# FTDI.net
KiCad netlist of a schematic drawn in Altium Designer
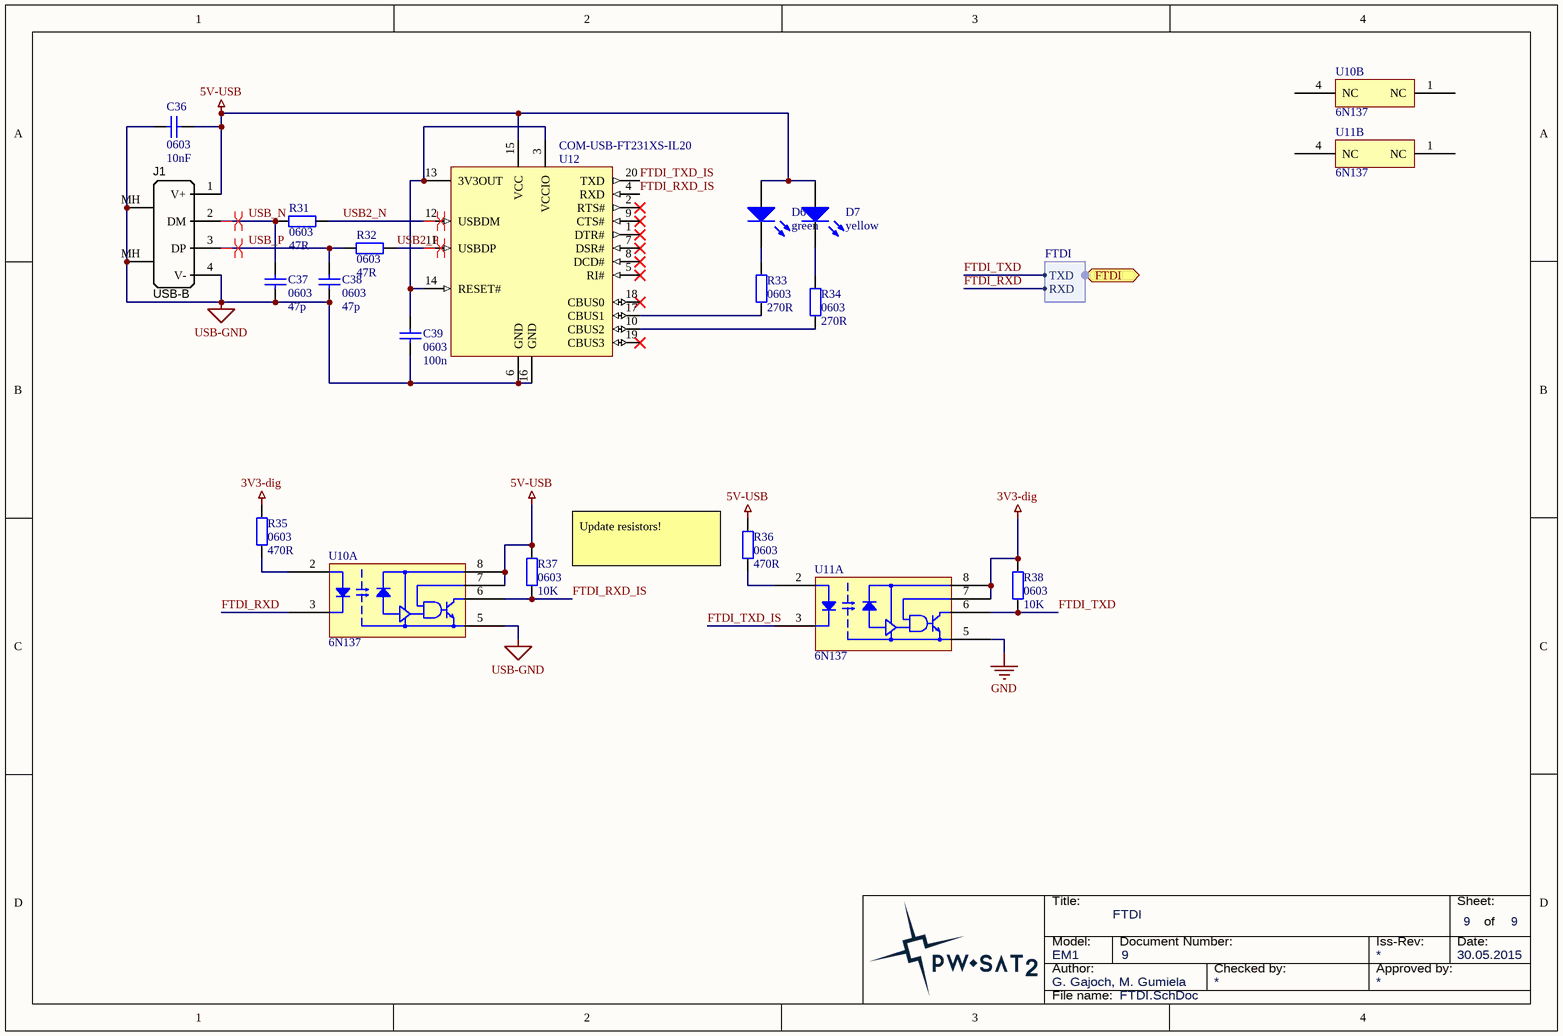
[diagram p0: FTDI.SchDoc]

(export (version "E")
  (design (tool "Eeschema 10.0.6"))
  (components
    (comp (ref "C36")
      (value "0603")
      (footprint "SMD_Capacitor_0603")
      (description "Capacitor")
      (fields (field (name "ALTIUM_VALUE") "10nF") (field (name "PUBLISHER") "Altium Limited"))
      (libsource (lib "Miscellaneous Devices") (part "Cap"))
    )
    (comp (ref "C37")
      (value "0603")
      (footprint "SMD_Capacitor_0603")
      (description "Capacitor")
      (fields (field (name "ALTIUM_VALUE") "47p") (field (name "PUBLISHER") "Altium Limited"))
      (libsource (lib "Miscellaneous Devices") (part "Cap"))
    )
    (comp (ref "C38")
      (value "0603")
      (footprint "SMD_Capacitor_0603")
      (description "Capacitor")
      (fields (field (name "ALTIUM_VALUE") "47p") (field (name "PUBLISHER") "Altium Limited"))
      (libsource (lib "Miscellaneous Devices") (part "Cap"))
    )
    (comp (ref "C39")
      (value "0603")
      (footprint "SMD_Capacitor_0603")
      (description "Capacitor")
      (fields (field (name "ALTIUM_VALUE") "100n") (field (name "PUBLISHER") "Altium Limited"))
      (libsource (lib "Miscellaneous Devices") (part "Cap"))
    )
    (comp (ref "D6")
      (value "green")
      (footprint "LED 0805 GREEN")
      (description "Typical RED, GREEN, YELLOW, AMBER GaAs LED")
      (fields (field (name "PUBLISHER") "Altium Limited"))
      (libsource (lib "Miscellaneous Devices") (part "LED2"))
    )
    (comp (ref "D7")
      (value "yellow")
      (footprint "LED 0805 Yellow")
      (description "Typical RED, GREEN, YELLOW, AMBER GaAs LED")
      (fields (field (name "PUBLISHER") "Altium Limited"))
      (libsource (lib "Miscellaneous Devices") (part "LED2"))
    )
    (comp (ref "J1")
      (value "USB-B")
      (footprint "USB_TypeB_Tyco")
      (description "Connector THT Type B USB connector")
      (libsource (lib "PBL - Connectors") (part "USB_TypeB"))
    )
    (comp (ref "R31")
      (value "0603")
      (footprint "SMD_Resistor_0603")
      (description "Resistor")
      (fields (field (name "ALTIUM_VALUE") "47R") (field (name "PUBLISHER") "Altium Limited"))
      (libsource (lib "Miscellaneous Devices") (part "Res2"))
    )
    (comp (ref "R32")
      (value "0603")
      (footprint "SMD_Resistor_0603")
      (description "Resistor")
      (fields (field (name "ALTIUM_VALUE") "47R") (field (name "PUBLISHER") "Altium Limited"))
      (libsource (lib "Miscellaneous Devices") (part "Res2"))
    )
    (comp (ref "R33")
      (value "0603")
      (footprint "SMD_Resistor_0603")
      (description "Resistor")
      (fields (field (name "ALTIUM_VALUE") "270R") (field (name "PUBLISHER") "Altium Limited"))
      (libsource (lib "") (part "Res2_1"))
    )
    (comp (ref "R34")
      (value "0603")
      (footprint "SMD_Resistor_0603")
      (description "Resistor")
      (fields (field (name "ALTIUM_VALUE") "270R") (field (name "PUBLISHER") "Altium Limited"))
      (libsource (lib "") (part "Res2_1"))
    )
    (comp (ref "R35")
      (value "0603")
      (footprint "SMD_Resistor_0603")
      (description "Resistor")
      (fields (field (name "ALTIUM_VALUE") "470R") (field (name "PUBLISHER") "Altium Limited"))
      (libsource (lib "") (part "Res2_1"))
    )
    (comp (ref "R36")
      (value "0603")
      (footprint "SMD_Resistor_0603")
      (description "Resistor")
      (fields (field (name "ALTIUM_VALUE") "470R") (field (name "PUBLISHER") "Altium Limited"))
      (libsource (lib "") (part "Res2_1"))
    )
    (comp (ref "R37")
      (value "0603")
      (footprint "SMD_Resistor_0603")
      (description "Resistor")
      (fields (field (name "ALTIUM_VALUE") "10K") (field (name "PUBLISHER") "Altium Limited"))
      (libsource (lib "") (part "Res2_1"))
    )
    (comp (ref "R38")
      (value "0603")
      (footprint "SMD_Resistor_0603")
      (description "Resistor")
      (fields (field (name "ALTIUM_VALUE") "10K") (field (name "PUBLISHER") "Altium Limited"))
      (libsource (lib "") (part "Res2_1"))
    )
    (comp (ref "U10")
      (value "6N137")
      (footprint "Surface Mount DIP 8-pin")
      (libsource (lib "6N137") (part "6N137"))
    )
    (comp (ref "U11")
      (value "6N137")
      (footprint "Surface Mount DIP 8-pin")
      (libsource (lib "6N137") (part "6N137"))
    )
    (comp (ref "U12")
      (value "COM-USB-FT231XS-IL20")
      (footprint "SSOP-20_L")
      (libsource (lib "COM-USB-FT231XS-IL20") (part "COM-USB-FT231XS-IL20"))
    )
  )
  (nets
    (net (code "2") (name "/FTDI_RXD") (class "Default")
      (node (ref "U10") (pin "3") (pinfunction "-_3") (pintype "passive"))
    )
    (net (code "3") (name "/FTDI_RXD_IS") (class "Default")
      (node (ref "R37") (pin "1") (pinfunction "1_1") (pintype "passive"))
      (node (ref "U10") (pin "6") (pinfunction "Vo_6") (pintype "passive"))
      (node (ref "U12") (pin "4") (pinfunction "RXD_4") (pintype "input"))
    )
    (net (code "4") (name "/FTDI_TXD") (class "Default")
      (node (ref "R38") (pin "1") (pinfunction "1_1") (pintype "passive"))
      (node (ref "U11") (pin "6") (pinfunction "Vo_6") (pintype "passive"))
    )
    (net (code "5") (name "/FTDI_TXD_IS") (class "Default")
      (node (ref "U11") (pin "3") (pinfunction "-_3") (pintype "passive"))
      (node (ref "U12") (pin "20") (pinfunction "TXD_20") (pintype "output"))
    )
    (net (code "6") (name "/USB2_N") (class "Default")
      (node (ref "R31") (pin "2") (pinfunction "2_2") (pintype "passive"))
      (node (ref "U12") (pin "12") (pinfunction "USBDM_12") (pintype "input"))
    )
    (net (code "7") (name "/USB2_P") (class "Default")
      (node (ref "R32") (pin "2") (pinfunction "2_2") (pintype "passive"))
      (node (ref "U12") (pin "11") (pinfunction "USBDP_11") (pintype "input"))
    )
    (net (code "8") (name "/USB_N") (class "Default")
      (node (ref "C37") (pin "2") (pinfunction "2_2") (pintype "passive"))
      (node (ref "J1") (pin "2") (pinfunction "DM_2") (pintype "passive"))
      (node (ref "R31") (pin "1") (pinfunction "1_1") (pintype "passive"))
    )
    (net (code "9") (name "/USB_P") (class "Default")
      (node (ref "C38") (pin "2") (pinfunction "2_2") (pintype "passive"))
      (node (ref "J1") (pin "3") (pinfunction "DP_3") (pintype "passive"))
      (node (ref "R32") (pin "1") (pinfunction "1_1") (pintype "passive"))
    )
    (net (code "11") (name "3V3-dig") (class "Default")
      (node (ref "R35") (pin "2") (pinfunction "2_2") (pintype "passive"))
      (node (ref "R38") (pin "2") (pinfunction "2_2") (pintype "passive"))
      (node (ref "U11") (pin "7") (pinfunction "Ve_7") (pintype "passive"))
      (node (ref "U11") (pin "8") (pinfunction "Vcc_8") (pintype "passive"))
    )
    (net (code "12") (name "5V-USB") (class "Default")
      (node (ref "C36") (pin "1") (pinfunction "1_1") (pintype "passive"))
      (node (ref "D6") (pin "1") (pinfunction "A_1") (pintype "passive"))
      (node (ref "D7") (pin "1") (pinfunction "A_1") (pintype "passive"))
      (node (ref "J1") (pin "1") (pinfunction "V+_1") (pintype "passive"))
      (node (ref "R36") (pin "2") (pinfunction "2_2") (pintype "passive"))
      (node (ref "R37") (pin "2") (pinfunction "2_2") (pintype "passive"))
      (node (ref "U10") (pin "7") (pinfunction "Ve_7") (pintype "passive"))
      (node (ref "U10") (pin "8") (pinfunction "Vcc_8") (pintype "passive"))
      (node (ref "U12") (pin "15") (pinfunction "VCC_15") (pintype "power_in"))
    )
    (net (code "13") (name "GND") (class "Default")
      (node (ref "U11") (pin "5") (pinfunction "GND_5") (pintype "passive"))
    )
    (net (code "14") (name "Net-(D6-K)") (class "Default")
      (node (ref "D6") (pin "2") (pinfunction "K_2") (pintype "passive"))
      (node (ref "R33") (pin "2") (pinfunction "2_2") (pintype "passive"))
    )
    (net (code "15") (name "Net-(D7-K)") (class "Default")
      (node (ref "D7") (pin "2") (pinfunction "K_2") (pintype "passive"))
      (node (ref "R34") (pin "2") (pinfunction "2_2") (pintype "passive"))
    )
    (net (code "16") (name "Net-(U10A-+)") (class "Default")
      (node (ref "R35") (pin "1") (pinfunction "1_1") (pintype "passive"))
      (node (ref "U10") (pin "2") (pinfunction "+_2") (pintype "passive"))
    )
    (net (code "17") (name "Net-(U11A-+)") (class "Default")
      (node (ref "R36") (pin "1") (pinfunction "1_1") (pintype "passive"))
      (node (ref "U11") (pin "2") (pinfunction "+_2") (pintype "passive"))
    )
    (net (code "18") (name "Net-(U12-3V3OUT)") (class "Default")
      (node (ref "C39") (pin "2") (pinfunction "2_2") (pintype "passive"))
      (node (ref "U12") (pin "13") (pinfunction "3V3OUT_13") (pintype "power_in"))
      (node (ref "U12") (pin "14") (pinfunction "RESET#_14") (pintype "input"))
      (node (ref "U12") (pin "3") (pinfunction "VCCIO_3") (pintype "power_in"))
    )
    (net (code "19") (name "Net-(U12-CBUS1)") (class "Default")
      (node (ref "R33") (pin "1") (pinfunction "1_1") (pintype "passive"))
      (node (ref "U12") (pin "17") (pinfunction "CBUS1_17") (pintype "bidirectional"))
    )
    (net (code "20") (name "Net-(U12-CBUS2)") (class "Default")
      (node (ref "R34") (pin "1") (pinfunction "1_1") (pintype "passive"))
      (node (ref "U12") (pin "10") (pinfunction "CBUS2_10") (pintype "bidirectional"))
    )
    (net (code "21") (name "USB-GND") (class "Default")
      (node (ref "C36") (pin "2") (pinfunction "2_2") (pintype "passive"))
      (node (ref "C37") (pin "1") (pinfunction "1_1") (pintype "passive"))
      (node (ref "C38") (pin "1") (pinfunction "1_1") (pintype "passive"))
      (node (ref "C39") (pin "1") (pinfunction "1_1") (pintype "passive"))
      (node (ref "J1") (pin "4") (pinfunction "V-_4") (pintype "passive"))
      (node (ref "J1") (pin "MH") (pinfunction "Shell_MH") (pintype "passive"))
      (node (ref "U10") (pin "5") (pinfunction "GND_5") (pintype "passive"))
      (node (ref "U12") (pin "16") (pinfunction "GND_16") (pintype "power_in"))
      (node (ref "U12") (pin "6") (pinfunction "GND_6") (pintype "power_in"))
    )
    (net (code "22") (name "unconnected-(U10B-NC-Pad1)") (class "Default")
      (node (ref "U10") (pin "1") (pinfunction "NC_1") (pintype "passive"))
    )
    (net (code "23") (name "unconnected-(U10B-NC-Pad4)") (class "Default")
      (node (ref "U10") (pin "4") (pinfunction "NC_4") (pintype "passive"))
    )
    (net (code "24") (name "unconnected-(U11B-NC-Pad1)") (class "Default")
      (node (ref "U11") (pin "1") (pinfunction "NC_1") (pintype "passive"))
    )
    (net (code "25") (name "unconnected-(U11B-NC-Pad4)") (class "Default")
      (node (ref "U11") (pin "4") (pinfunction "NC_4") (pintype "passive"))
    )
    (net (code "26") (name "unconnected-(U12-CBUS0-Pad18)") (class "Default")
      (node (ref "U12") (pin "18") (pinfunction "CBUS0_18") (pintype "bidirectional+no_connect"))
    )
    (net (code "27") (name "unconnected-(U12-CBUS3-Pad19)") (class "Default")
      (node (ref "U12") (pin "19") (pinfunction "CBUS3_19") (pintype "bidirectional+no_connect"))
    )
    (net (code "28") (name "unconnected-(U12-CTS#-Pad9)") (class "Default")
      (node (ref "U12") (pin "9") (pinfunction "CTS#_9") (pintype "input+no_connect"))
    )
    (net (code "29") (name "unconnected-(U12-DCD#-Pad8)") (class "Default")
      (node (ref "U12") (pin "8") (pinfunction "DCD#_8") (pintype "input+no_connect"))
    )
    (net (code "30") (name "unconnected-(U12-DSR#-Pad7)") (class "Default")
      (node (ref "U12") (pin "7") (pinfunction "DSR#_7") (pintype "input+no_connect"))
    )
    (net (code "31") (name "unconnected-(U12-DTR#-Pad1)") (class "Default")
      (node (ref "U12") (pin "1") (pinfunction "DTR#_1") (pintype "output+no_connect"))
    )
    (net (code "32") (name "unconnected-(U12-RI#-Pad5)") (class "Default")
      (node (ref "U12") (pin "5") (pinfunction "RI#_5") (pintype "input+no_connect"))
    )
    (net (code "33") (name "unconnected-(U12-RTS#-Pad2)") (class "Default")
      (node (ref "U12") (pin "2") (pinfunction "RTS#_2") (pintype "output+no_connect"))
    )
  )
)
